# quad_decay_v1_0_1.net
KiCad netlist of a schematic drawn in EAGLE
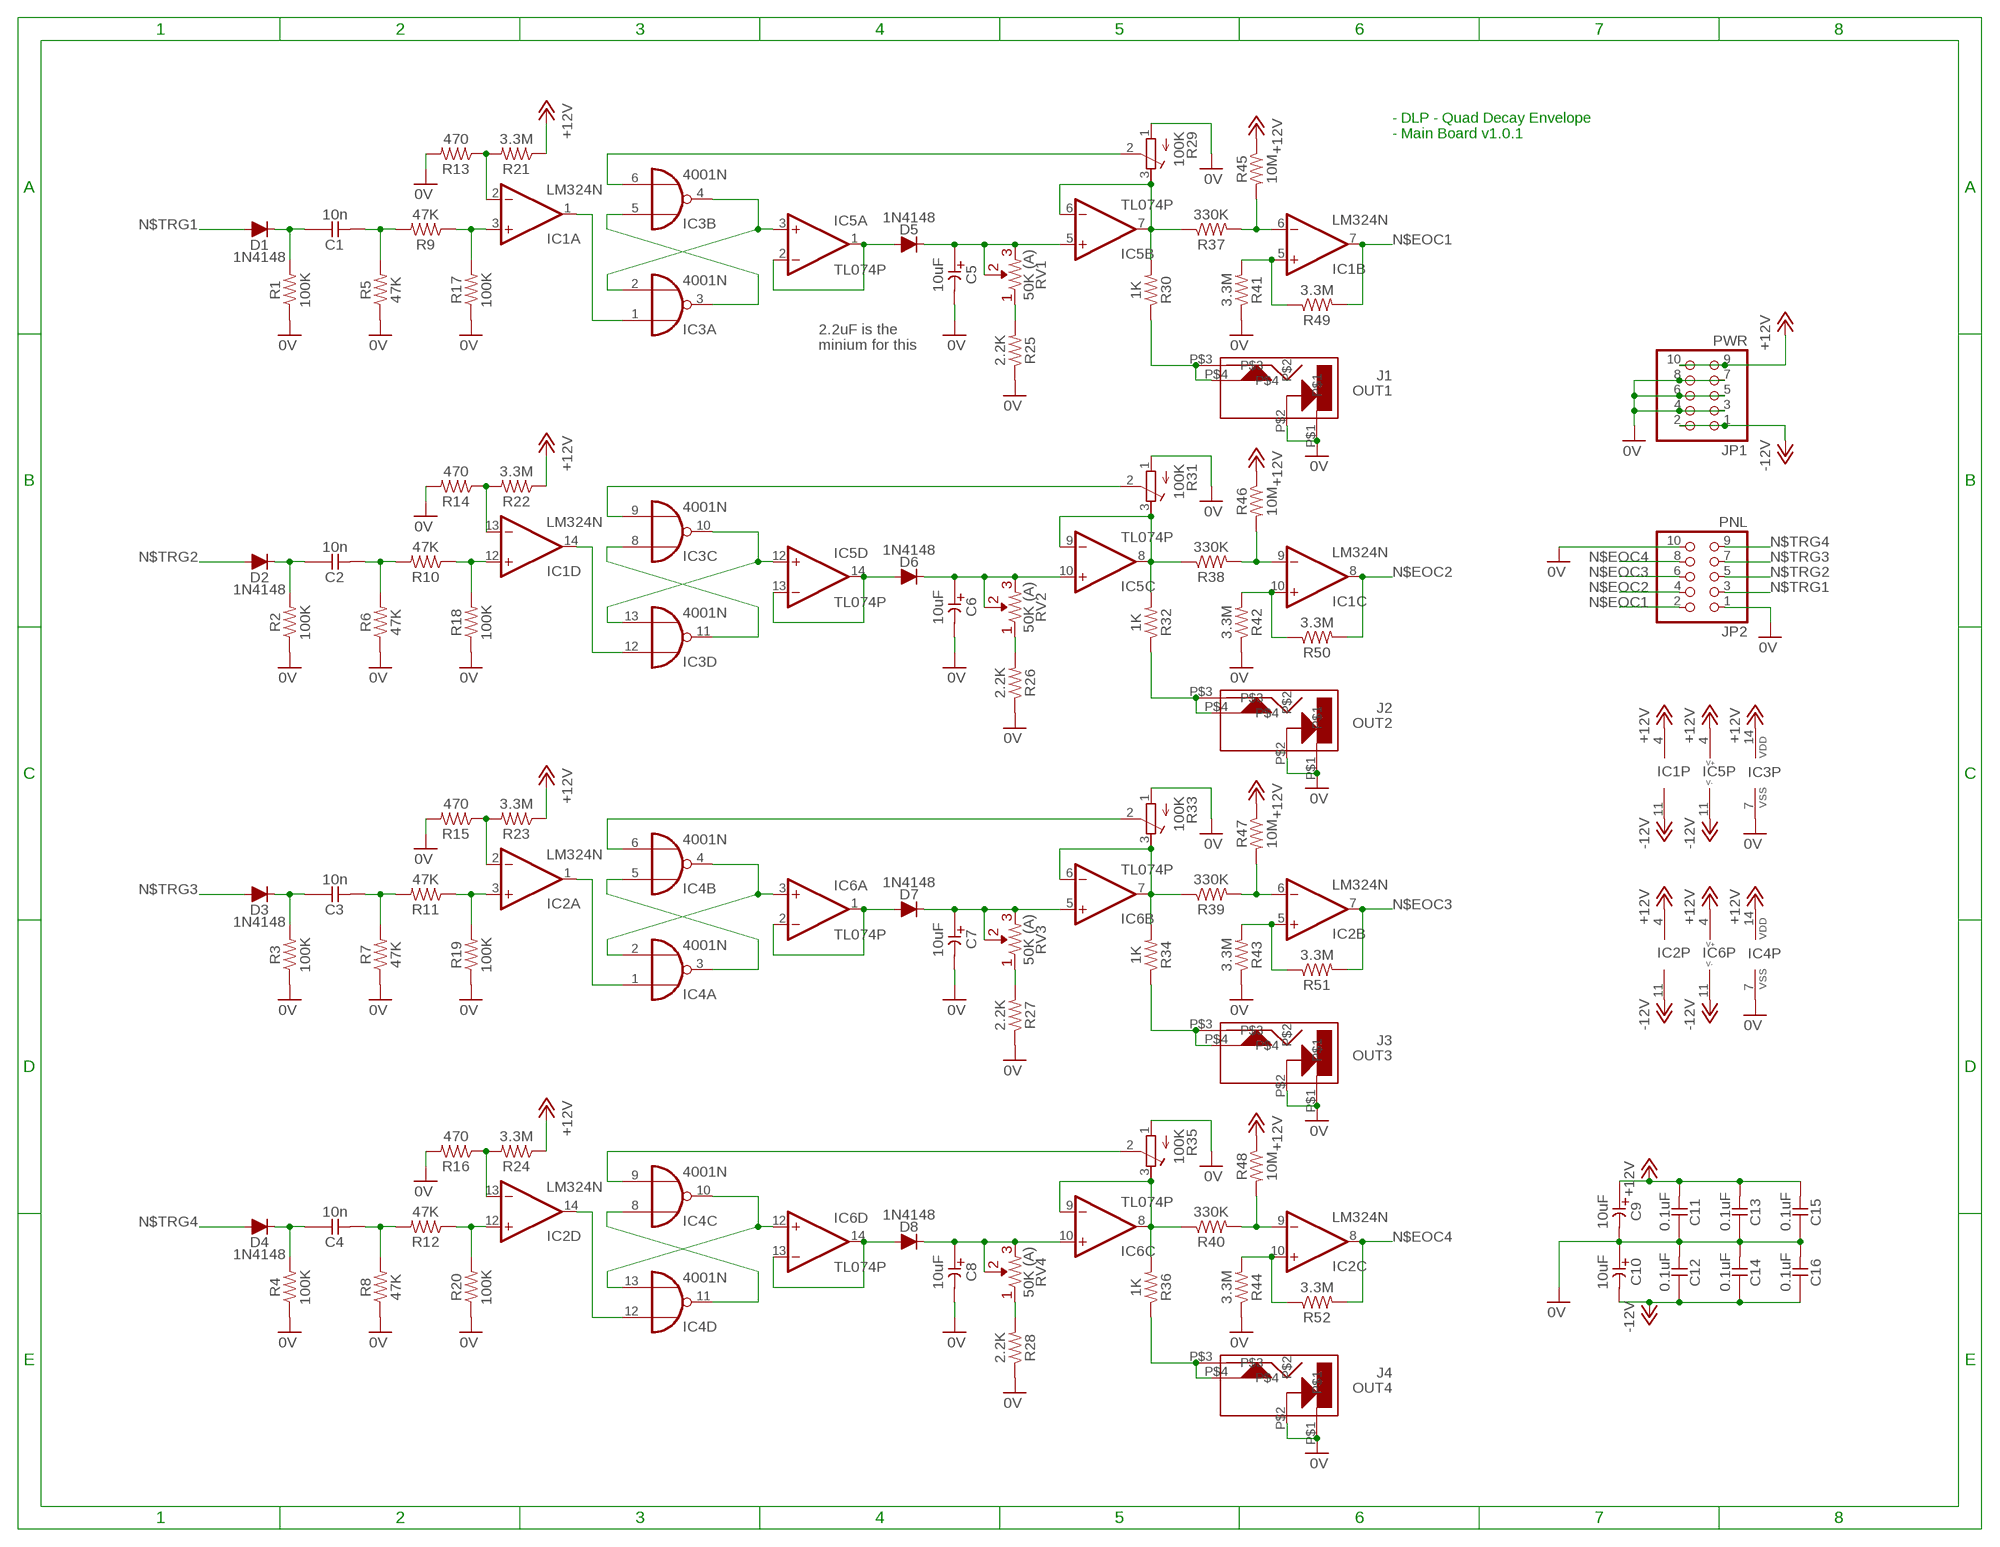
[diagram p0: schematic, sheet 1]

(export (version "E")
  (design (tool "Eeschema 10.0.6"))
  (components
    (comp (ref "C1")
      (value "10n")
      (footprint "eagle-import:C025-024X044")
      (libsource (lib "eagle-import") (part "CC-US025-024X044"))
    )
    (comp (ref "C2")
      (value "10n")
      (footprint "eagle-import:C025-024X044")
      (libsource (lib "eagle-import") (part "CC-US025-024X044"))
    )
    (comp (ref "C3")
      (value "10n")
      (footprint "eagle-import:C025-024X044")
      (libsource (lib "eagle-import") (part "CC-US025-024X044"))
    )
    (comp (ref "C4")
      (value "10n")
      (footprint "eagle-import:C025-024X044")
      (libsource (lib "eagle-import") (part "CC-US025-024X044"))
    )
    (comp (ref "C5")
      (value "10uF")
      (footprint "eagle-import:E2-5")
      (libsource (lib "eagle-import") (part "CE-USE2-5"))
    )
    (comp (ref "C6")
      (value "10uF")
      (footprint "eagle-import:E2-5")
      (libsource (lib "eagle-import") (part "CE-USE2-5"))
    )
    (comp (ref "C7")
      (value "10uF")
      (footprint "eagle-import:E2-5")
      (libsource (lib "eagle-import") (part "CE-USE2-5"))
    )
    (comp (ref "C8")
      (value "10uF")
      (footprint "eagle-import:E2-5")
      (libsource (lib "eagle-import") (part "CE-USE2-5"))
    )
    (comp (ref "C9")
      (value "10uF")
      (footprint "eagle-import:E2-5")
      (libsource (lib "eagle-import") (part "CE-USE2-5"))
    )
    (comp (ref "C10")
      (value "10uF")
      (footprint "eagle-import:E2-5")
      (libsource (lib "eagle-import") (part "CE-USE2-5"))
    )
    (comp (ref "C11")
      (value "0.1uF")
      (footprint "eagle-import:C025-024X044")
      (libsource (lib "eagle-import") (part "CC-US025-024X044"))
    )
    (comp (ref "C12")
      (value "0.1uF")
      (footprint "eagle-import:C025-024X044")
      (libsource (lib "eagle-import") (part "CC-US025-024X044"))
    )
    (comp (ref "C13")
      (value "0.1uF")
      (footprint "eagle-import:C025-024X044")
      (libsource (lib "eagle-import") (part "CC-US025-024X044"))
    )
    (comp (ref "C14")
      (value "0.1uF")
      (footprint "eagle-import:C025-024X044")
      (libsource (lib "eagle-import") (part "CC-US025-024X044"))
    )
    (comp (ref "C15")
      (value "0.1uF")
      (footprint "eagle-import:C025-024X044")
      (libsource (lib "eagle-import") (part "CC-US025-024X044"))
    )
    (comp (ref "C16")
      (value "0.1uF")
      (footprint "eagle-import:C025-024X044")
      (libsource (lib "eagle-import") (part "CC-US025-024X044"))
    )
    (comp (ref "D1")
      (value "1N4148")
      (footprint "eagle-import:DO34-5")
      (libsource (lib "eagle-import") (part "1N4148"))
    )
    (comp (ref "D2")
      (value "1N4148")
      (footprint "eagle-import:DO34-5")
      (libsource (lib "eagle-import") (part "1N4148"))
    )
    (comp (ref "D3")
      (value "1N4148")
      (footprint "eagle-import:DO34-5")
      (libsource (lib "eagle-import") (part "1N4148"))
    )
    (comp (ref "D4")
      (value "1N4148")
      (footprint "eagle-import:DO34-5")
      (libsource (lib "eagle-import") (part "1N4148"))
    )
    (comp (ref "D5")
      (value "1N4148")
      (footprint "eagle-import:DO34-5")
      (libsource (lib "eagle-import") (part "1N4148"))
    )
    (comp (ref "D6")
      (value "1N4148")
      (footprint "eagle-import:DO34-5")
      (libsource (lib "eagle-import") (part "1N4148"))
    )
    (comp (ref "D7")
      (value "1N4148")
      (footprint "eagle-import:DO34-5")
      (libsource (lib "eagle-import") (part "1N4148"))
    )
    (comp (ref "D8")
      (value "1N4148")
      (footprint "eagle-import:DO34-5")
      (libsource (lib "eagle-import") (part "1N4148"))
    )
    (comp (ref "IC1")
      (value "LM324N")
      (footprint "eagle-import:DIL14")
      (libsource (lib "eagle-import") (part "LM324N"))
    )
    (comp (ref "IC2")
      (value "LM324N")
      (footprint "eagle-import:DIL14")
      (libsource (lib "eagle-import") (part "LM324N"))
    )
    (comp (ref "IC3")
      (value "4001N")
      (footprint "eagle-import:DIL14")
      (libsource (lib "eagle-import") (part "4001N"))
    )
    (comp (ref "IC4")
      (value "4001N")
      (footprint "eagle-import:DIL14")
      (libsource (lib "eagle-import") (part "4001N"))
    )
    (comp (ref "IC5")
      (value "TL074P")
      (footprint "eagle-import:DIL14")
      (libsource (lib "eagle-import") (part "TL074P"))
    )
    (comp (ref "IC6")
      (value "TL074P")
      (footprint "eagle-import:DIL14")
      (libsource (lib "eagle-import") (part "TL074P"))
    )
    (comp (ref "J1")
      (value "OUT1")
      (footprint "eagle-import:CL1384")
      (libsource (lib "eagle-import") (part "CL1384"))
    )
    (comp (ref "J2")
      (value "OUT2")
      (footprint "eagle-import:CL1384")
      (libsource (lib "eagle-import") (part "CL1384"))
    )
    (comp (ref "J3")
      (value "OUT3")
      (footprint "eagle-import:CL1384")
      (libsource (lib "eagle-import") (part "CL1384"))
    )
    (comp (ref "J4")
      (value "OUT4")
      (footprint "eagle-import:CL1384")
      (libsource (lib "eagle-import") (part "CL1384"))
    )
    (comp (ref "JP1")
      (value "PWR")
      (footprint "eagle-import:2X05")
      (libsource (lib "eagle-import") (part "PINHD-2X5"))
    )
    (comp (ref "JP2")
      (value "PNL")
      (footprint "eagle-import:2X05")
      (libsource (lib "eagle-import") (part "PINHD-2X5"))
    )
    (comp (ref "R1")
      (value "100K")
      (footprint "eagle-import:0207_7")
      (libsource (lib "eagle-import") (part "R"))
    )
    (comp (ref "R2")
      (value "100K")
      (footprint "eagle-import:0207_7")
      (libsource (lib "eagle-import") (part "R"))
    )
    (comp (ref "R3")
      (value "100K")
      (footprint "eagle-import:0207_7")
      (libsource (lib "eagle-import") (part "R"))
    )
    (comp (ref "R4")
      (value "100K")
      (footprint "eagle-import:0207_7")
      (libsource (lib "eagle-import") (part "R"))
    )
    (comp (ref "R5")
      (value "47K")
      (footprint "eagle-import:0207_7")
      (libsource (lib "eagle-import") (part "R"))
    )
    (comp (ref "R6")
      (value "47K")
      (footprint "eagle-import:0207_7")
      (libsource (lib "eagle-import") (part "R"))
    )
    (comp (ref "R7")
      (value "47K")
      (footprint "eagle-import:0207_7")
      (libsource (lib "eagle-import") (part "R"))
    )
    (comp (ref "R8")
      (value "47K")
      (footprint "eagle-import:0207_7")
      (libsource (lib "eagle-import") (part "R"))
    )
    (comp (ref "R9")
      (value "47K")
      (footprint "eagle-import:0207_7")
      (libsource (lib "eagle-import") (part "R"))
    )
    (comp (ref "R10")
      (value "47K")
      (footprint "eagle-import:0207_7")
      (libsource (lib "eagle-import") (part "R"))
    )
    (comp (ref "R11")
      (value "47K")
      (footprint "eagle-import:0207_7")
      (libsource (lib "eagle-import") (part "R"))
    )
    (comp (ref "R12")
      (value "47K")
      (footprint "eagle-import:0207_7")
      (libsource (lib "eagle-import") (part "R"))
    )
    (comp (ref "R13")
      (value "470")
      (footprint "eagle-import:0207_7")
      (libsource (lib "eagle-import") (part "R"))
    )
    (comp (ref "R14")
      (value "470")
      (footprint "eagle-import:0207_7")
      (libsource (lib "eagle-import") (part "R"))
    )
    (comp (ref "R15")
      (value "470")
      (footprint "eagle-import:0207_7")
      (libsource (lib "eagle-import") (part "R"))
    )
    (comp (ref "R16")
      (value "470")
      (footprint "eagle-import:0207_7")
      (libsource (lib "eagle-import") (part "R"))
    )
    (comp (ref "R17")
      (value "100K")
      (footprint "eagle-import:0207_7")
      (libsource (lib "eagle-import") (part "R"))
    )
    (comp (ref "R18")
      (value "100K")
      (footprint "eagle-import:0207_7")
      (libsource (lib "eagle-import") (part "R"))
    )
    (comp (ref "R19")
      (value "100K")
      (footprint "eagle-import:0207_7")
      (libsource (lib "eagle-import") (part "R"))
    )
    (comp (ref "R20")
      (value "100K")
      (footprint "eagle-import:0207_7")
      (libsource (lib "eagle-import") (part "R"))
    )
    (comp (ref "R21")
      (value "3.3M")
      (footprint "eagle-import:0207_7")
      (libsource (lib "eagle-import") (part "R"))
    )
    (comp (ref "R22")
      (value "3.3M")
      (footprint "eagle-import:0207_7")
      (libsource (lib "eagle-import") (part "R"))
    )
    (comp (ref "R23")
      (value "3.3M")
      (footprint "eagle-import:0207_7")
      (libsource (lib "eagle-import") (part "R"))
    )
    (comp (ref "R24")
      (value "3.3M")
      (footprint "eagle-import:0207_7")
      (libsource (lib "eagle-import") (part "R"))
    )
    (comp (ref "R25")
      (value "2.2K")
      (footprint "eagle-import:0207_7")
      (libsource (lib "eagle-import") (part "R"))
    )
    (comp (ref "R26")
      (value "2.2K")
      (footprint "eagle-import:0207_7")
      (libsource (lib "eagle-import") (part "R"))
    )
    (comp (ref "R27")
      (value "2.2K")
      (footprint "eagle-import:0207_7")
      (libsource (lib "eagle-import") (part "R"))
    )
    (comp (ref "R28")
      (value "2.2K")
      (footprint "eagle-import:0207_7")
      (libsource (lib "eagle-import") (part "R"))
    )
    (comp (ref "R29")
      (value "100K")
      (footprint "eagle-import:RTRIM3339P")
      (libsource (lib "eagle-import") (part "R-TRIMM3339P"))
    )
    (comp (ref "R30")
      (value "1K")
      (footprint "eagle-import:0207_7")
      (libsource (lib "eagle-import") (part "R"))
    )
    (comp (ref "R31")
      (value "100K")
      (footprint "eagle-import:RTRIM3339P")
      (libsource (lib "eagle-import") (part "R-TRIMM3339P"))
    )
    (comp (ref "R32")
      (value "1K")
      (footprint "eagle-import:0207_7")
      (libsource (lib "eagle-import") (part "R"))
    )
    (comp (ref "R33")
      (value "100K")
      (footprint "eagle-import:RTRIM3339P")
      (libsource (lib "eagle-import") (part "R-TRIMM3339P"))
    )
    (comp (ref "R34")
      (value "1K")
      (footprint "eagle-import:0207_7")
      (libsource (lib "eagle-import") (part "R"))
    )
    (comp (ref "R35")
      (value "100K")
      (footprint "eagle-import:RTRIM3339P")
      (libsource (lib "eagle-import") (part "R-TRIMM3339P"))
    )
    (comp (ref "R36")
      (value "1K")
      (footprint "eagle-import:0207_7")
      (libsource (lib "eagle-import") (part "R"))
    )
    (comp (ref "R37")
      (value "330K")
      (footprint "eagle-import:0207_7")
      (libsource (lib "eagle-import") (part "R"))
    )
    (comp (ref "R38")
      (value "330K")
      (footprint "eagle-import:0207_7")
      (libsource (lib "eagle-import") (part "R"))
    )
    (comp (ref "R39")
      (value "330K")
      (footprint "eagle-import:0207_7")
      (libsource (lib "eagle-import") (part "R"))
    )
    (comp (ref "R40")
      (value "330K")
      (footprint "eagle-import:0207_7")
      (libsource (lib "eagle-import") (part "R"))
    )
    (comp (ref "R41")
      (value "3.3M")
      (footprint "eagle-import:0207_7")
      (libsource (lib "eagle-import") (part "R"))
    )
    (comp (ref "R42")
      (value "3.3M")
      (footprint "eagle-import:0207_7")
      (libsource (lib "eagle-import") (part "R"))
    )
    (comp (ref "R43")
      (value "3.3M")
      (footprint "eagle-import:0207_7")
      (libsource (lib "eagle-import") (part "R"))
    )
    (comp (ref "R44")
      (value "3.3M")
      (footprint "eagle-import:0207_7")
      (libsource (lib "eagle-import") (part "R"))
    )
    (comp (ref "R45")
      (value "10M")
      (footprint "eagle-import:0207_7")
      (libsource (lib "eagle-import") (part "R"))
    )
    (comp (ref "R46")
      (value "10M")
      (footprint "eagle-import:0207_7")
      (libsource (lib "eagle-import") (part "R"))
    )
    (comp (ref "R47")
      (value "10M")
      (footprint "eagle-import:0207_7")
      (libsource (lib "eagle-import") (part "R"))
    )
    (comp (ref "R48")
      (value "10M")
      (footprint "eagle-import:0207_7")
      (libsource (lib "eagle-import") (part "R"))
    )
    (comp (ref "R49")
      (value "3.3M")
      (footprint "eagle-import:0207_7")
      (libsource (lib "eagle-import") (part "R"))
    )
    (comp (ref "R50")
      (value "3.3M")
      (footprint "eagle-import:0207_7")
      (libsource (lib "eagle-import") (part "R"))
    )
    (comp (ref "R51")
      (value "3.3M")
      (footprint "eagle-import:0207_7")
      (libsource (lib "eagle-import") (part "R"))
    )
    (comp (ref "R52")
      (value "3.3M")
      (footprint "eagle-import:0207_7")
      (libsource (lib "eagle-import") (part "R"))
    )
    (comp (ref "RV1")
      (value "50K (A)")
      (footprint "eagle-import:R-VAR")
      (libsource (lib "eagle-import") (part "R-VAR"))
    )
    (comp (ref "RV2")
      (value "50K (A)")
      (footprint "eagle-import:R-VAR")
      (libsource (lib "eagle-import") (part "R-VAR"))
    )
    (comp (ref "RV3")
      (value "50K (A)")
      (footprint "eagle-import:R-VAR")
      (libsource (lib "eagle-import") (part "R-VAR"))
    )
    (comp (ref "RV4")
      (value "50K (A)")
      (footprint "eagle-import:R-VAR")
      (libsource (lib "eagle-import") (part "R-VAR"))
    )
  )
  (nets
    (net (code "1") (name "+12V") (class "Default")
      (node (ref "C11") (pin "2") (pinfunction "2_2") (pintype "passive"))
      (node (ref "C13") (pin "2") (pinfunction "2_2") (pintype "passive"))
      (node (ref "C15") (pin "2") (pinfunction "2_2") (pintype "passive"))
      (node (ref "C9") (pin "+") (pinfunction "+_+") (pintype "passive"))
      (node (ref "IC1") (pin "4") (pinfunction "V+_4") (pintype "power_in"))
      (node (ref "IC2") (pin "4") (pinfunction "V+_4") (pintype "power_in"))
      (node (ref "IC3") (pin "14") (pinfunction "VDD_14") (pintype "power_in"))
      (node (ref "IC4") (pin "14") (pinfunction "VDD_14") (pintype "power_in"))
      (node (ref "IC5") (pin "4") (pinfunction "V+_4") (pintype "power_in"))
      (node (ref "IC6") (pin "4") (pinfunction "V+_4") (pintype "power_in"))
      (node (ref "JP1") (pin "10") (pinfunction "10_10") (pintype "passive"))
      (node (ref "JP1") (pin "9") (pinfunction "9_9") (pintype "passive"))
      (node (ref "R21") (pin "1") (pinfunction "1_1") (pintype "passive"))
      (node (ref "R22") (pin "1") (pinfunction "1_1") (pintype "passive"))
      (node (ref "R23") (pin "1") (pinfunction "1_1") (pintype "passive"))
      (node (ref "R24") (pin "1") (pinfunction "1_1") (pintype "passive"))
      (node (ref "R45") (pin "1") (pinfunction "1_1") (pintype "passive"))
      (node (ref "R46") (pin "1") (pinfunction "1_1") (pintype "passive"))
      (node (ref "R47") (pin "1") (pinfunction "1_1") (pintype "passive"))
      (node (ref "R48") (pin "1") (pinfunction "1_1") (pintype "passive"))
    )
    (net (code "2") (name "-12V") (class "Default")
      (node (ref "C10") (pin "-") (pinfunction "-_-") (pintype "passive"))
      (node (ref "C12") (pin "1") (pinfunction "1_1") (pintype "passive"))
      (node (ref "C14") (pin "1") (pinfunction "1_1") (pintype "passive"))
      (node (ref "C16") (pin "1") (pinfunction "1_1") (pintype "passive"))
      (node (ref "IC1") (pin "11") (pinfunction "V-_11") (pintype "power_in"))
      (node (ref "IC2") (pin "11") (pinfunction "V-_11") (pintype "power_in"))
      (node (ref "IC5") (pin "11") (pinfunction "V-_11") (pintype "power_in"))
      (node (ref "IC6") (pin "11") (pinfunction "V-_11") (pintype "power_in"))
      (node (ref "JP1") (pin "1") (pinfunction "1_1") (pintype "passive"))
      (node (ref "JP1") (pin "2") (pinfunction "2_2") (pintype "passive"))
    )
    (net (code "3") (name "/N$EOC1") (class "Default")
      (node (ref "IC1") (pin "7") (pinfunction "OUT_7") (pintype "output"))
      (node (ref "JP2") (pin "2") (pinfunction "2_2") (pintype "passive"))
      (node (ref "R49") (pin "2") (pinfunction "2_2") (pintype "passive"))
    )
    (net (code "4") (name "/N$EOC2") (class "Default")
      (node (ref "IC1") (pin "8") (pinfunction "OUT_8") (pintype "output"))
      (node (ref "JP2") (pin "4") (pinfunction "4_4") (pintype "passive"))
      (node (ref "R50") (pin "2") (pinfunction "2_2") (pintype "passive"))
    )
    (net (code "5") (name "/N$EOC3") (class "Default")
      (node (ref "IC2") (pin "7") (pinfunction "OUT_7") (pintype "output"))
      (node (ref "JP2") (pin "6") (pinfunction "6_6") (pintype "passive"))
      (node (ref "R51") (pin "2") (pinfunction "2_2") (pintype "passive"))
    )
    (net (code "6") (name "/N$EOC4") (class "Default")
      (node (ref "IC2") (pin "8") (pinfunction "OUT_8") (pintype "output"))
      (node (ref "JP2") (pin "8") (pinfunction "8_8") (pintype "passive"))
      (node (ref "R52") (pin "2") (pinfunction "2_2") (pintype "passive"))
    )
    (net (code "7") (name "/N$TRG1") (class "Default")
      (node (ref "D1") (pin "A") (pinfunction "A_A") (pintype "passive"))
      (node (ref "JP2") (pin "3") (pinfunction "3_3") (pintype "passive"))
    )
    (net (code "8") (name "/N$TRG2") (class "Default")
      (node (ref "D2") (pin "A") (pinfunction "A_A") (pintype "passive"))
      (node (ref "JP2") (pin "5") (pinfunction "5_5") (pintype "passive"))
    )
    (net (code "9") (name "/N$TRG3") (class "Default")
      (node (ref "D3") (pin "A") (pinfunction "A_A") (pintype "passive"))
      (node (ref "JP2") (pin "7") (pinfunction "7_7") (pintype "passive"))
    )
    (net (code "10") (name "/N$TRG4") (class "Default")
      (node (ref "D4") (pin "A") (pinfunction "A_A") (pintype "passive"))
      (node (ref "JP2") (pin "9") (pinfunction "9_9") (pintype "passive"))
    )
    (net (code "11") (name "0V") (class "Default")
      (node (ref "C10") (pin "+") (pinfunction "+_+") (pintype "passive"))
      (node (ref "C11") (pin "1") (pinfunction "1_1") (pintype "passive"))
      (node (ref "C12") (pin "2") (pinfunction "2_2") (pintype "passive"))
      (node (ref "C13") (pin "1") (pinfunction "1_1") (pintype "passive"))
      (node (ref "C14") (pin "2") (pinfunction "2_2") (pintype "passive"))
      (node (ref "C15") (pin "1") (pinfunction "1_1") (pintype "passive"))
      (node (ref "C16") (pin "2") (pinfunction "2_2") (pintype "passive"))
      (node (ref "C5") (pin "-") (pinfunction "-_-") (pintype "passive"))
      (node (ref "C6") (pin "-") (pinfunction "-_-") (pintype "passive"))
      (node (ref "C7") (pin "-") (pinfunction "-_-") (pintype "passive"))
      (node (ref "C8") (pin "-") (pinfunction "-_-") (pintype "passive"))
      (node (ref "C9") (pin "-") (pinfunction "-_-") (pintype "passive"))
      (node (ref "IC3") (pin "7") (pinfunction "VSS_7") (pintype "power_in"))
      (node (ref "IC4") (pin "7") (pinfunction "VSS_7") (pintype "power_in"))
      (node (ref "J1") (pin "P$1") (pinfunction "P$1_P$1") (pintype "bidirectional"))
      (node (ref "J1") (pin "P$2") (pinfunction "P$2_P$2") (pintype "bidirectional"))
      (node (ref "J2") (pin "P$1") (pinfunction "P$1_P$1") (pintype "bidirectional"))
      (node (ref "J2") (pin "P$2") (pinfunction "P$2_P$2") (pintype "bidirectional"))
      (node (ref "J3") (pin "P$1") (pinfunction "P$1_P$1") (pintype "bidirectional"))
      (node (ref "J3") (pin "P$2") (pinfunction "P$2_P$2") (pintype "bidirectional"))
      (node (ref "J4") (pin "P$1") (pinfunction "P$1_P$1") (pintype "bidirectional"))
      (node (ref "J4") (pin "P$2") (pinfunction "P$2_P$2") (pintype "bidirectional"))
      (node (ref "JP1") (pin "3") (pinfunction "3_3") (pintype "passive"))
      (node (ref "JP1") (pin "4") (pinfunction "4_4") (pintype "passive"))
      (node (ref "JP1") (pin "5") (pinfunction "5_5") (pintype "passive"))
      (node (ref "JP1") (pin "6") (pinfunction "6_6") (pintype "passive"))
      (node (ref "JP1") (pin "7") (pinfunction "7_7") (pintype "passive"))
      (node (ref "JP1") (pin "8") (pinfunction "8_8") (pintype "passive"))
      (node (ref "JP2") (pin "1") (pinfunction "1_1") (pintype "passive"))
      (node (ref "JP2") (pin "10") (pinfunction "10_10") (pintype "passive"))
      (node (ref "R1") (pin "1") (pinfunction "1_1") (pintype "passive"))
      (node (ref "R13") (pin "2") (pinfunction "2_2") (pintype "passive"))
      (node (ref "R14") (pin "2") (pinfunction "2_2") (pintype "passive"))
      (node (ref "R15") (pin "2") (pinfunction "2_2") (pintype "passive"))
      (node (ref "R16") (pin "2") (pinfunction "2_2") (pintype "passive"))
      (node (ref "R17") (pin "1") (pinfunction "1_1") (pintype "passive"))
      (node (ref "R18") (pin "1") (pinfunction "1_1") (pintype "passive"))
      (node (ref "R19") (pin "1") (pinfunction "1_1") (pintype "passive"))
      (node (ref "R2") (pin "1") (pinfunction "1_1") (pintype "passive"))
      (node (ref "R20") (pin "1") (pinfunction "1_1") (pintype "passive"))
      (node (ref "R25") (pin "1") (pinfunction "1_1") (pintype "passive"))
      (node (ref "R26") (pin "1") (pinfunction "1_1") (pintype "passive"))
      (node (ref "R27") (pin "1") (pinfunction "1_1") (pintype "passive"))
      (node (ref "R28") (pin "1") (pinfunction "1_1") (pintype "passive"))
      (node (ref "R29") (pin "1") (pinfunction "A_1") (pintype "passive"))
      (node (ref "R3") (pin "1") (pinfunction "1_1") (pintype "passive"))
      (node (ref "R31") (pin "1") (pinfunction "A_1") (pintype "passive"))
      (node (ref "R33") (pin "1") (pinfunction "A_1") (pintype "passive"))
      (node (ref "R35") (pin "1") (pinfunction "A_1") (pintype "passive"))
      (node (ref "R4") (pin "1") (pinfunction "1_1") (pintype "passive"))
      (node (ref "R41") (pin "1") (pinfunction "1_1") (pintype "passive"))
      (node (ref "R42") (pin "1") (pinfunction "1_1") (pintype "passive"))
      (node (ref "R43") (pin "1") (pinfunction "1_1") (pintype "passive"))
      (node (ref "R44") (pin "1") (pinfunction "1_1") (pintype "passive"))
      (node (ref "R5") (pin "1") (pinfunction "1_1") (pintype "passive"))
      (node (ref "R6") (pin "1") (pinfunction "1_1") (pintype "passive"))
      (node (ref "R7") (pin "1") (pinfunction "1_1") (pintype "passive"))
      (node (ref "R8") (pin "1") (pinfunction "1_1") (pintype "passive"))
    )
    (net (code "12") (name "Net-(C1-Pad1)") (class "Default")
      (node (ref "C1") (pin "1") (pinfunction "1_1") (pintype "passive"))
      (node (ref "D1") (pin "C") (pinfunction "C_C") (pintype "passive"))
      (node (ref "R1") (pin "2") (pinfunction "2_2") (pintype "passive"))
    )
    (net (code "13") (name "Net-(C1-Pad2)") (class "Default")
      (node (ref "C1") (pin "2") (pinfunction "2_2") (pintype "passive"))
      (node (ref "R5") (pin "2") (pinfunction "2_2") (pintype "passive"))
      (node (ref "R9") (pin "2") (pinfunction "2_2") (pintype "passive"))
    )
    (net (code "14") (name "Net-(C2-Pad1)") (class "Default")
      (node (ref "C2") (pin "1") (pinfunction "1_1") (pintype "passive"))
      (node (ref "D2") (pin "C") (pinfunction "C_C") (pintype "passive"))
      (node (ref "R2") (pin "2") (pinfunction "2_2") (pintype "passive"))
    )
    (net (code "15") (name "Net-(C2-Pad2)") (class "Default")
      (node (ref "C2") (pin "2") (pinfunction "2_2") (pintype "passive"))
      (node (ref "R10") (pin "2") (pinfunction "2_2") (pintype "passive"))
      (node (ref "R6") (pin "2") (pinfunction "2_2") (pintype "passive"))
    )
    (net (code "16") (name "Net-(C3-Pad1)") (class "Default")
      (node (ref "C3") (pin "1") (pinfunction "1_1") (pintype "passive"))
      (node (ref "D3") (pin "C") (pinfunction "C_C") (pintype "passive"))
      (node (ref "R3") (pin "2") (pinfunction "2_2") (pintype "passive"))
    )
    (net (code "17") (name "Net-(C3-Pad2)") (class "Default")
      (node (ref "C3") (pin "2") (pinfunction "2_2") (pintype "passive"))
      (node (ref "R11") (pin "2") (pinfunction "2_2") (pintype "passive"))
      (node (ref "R7") (pin "2") (pinfunction "2_2") (pintype "passive"))
    )
    (net (code "18") (name "Net-(C4-Pad1)") (class "Default")
      (node (ref "C4") (pin "1") (pinfunction "1_1") (pintype "passive"))
      (node (ref "D4") (pin "C") (pinfunction "C_C") (pintype "passive"))
      (node (ref "R4") (pin "2") (pinfunction "2_2") (pintype "passive"))
    )
    (net (code "19") (name "Net-(C4-Pad2)") (class "Default")
      (node (ref "C4") (pin "2") (pinfunction "2_2") (pintype "passive"))
      (node (ref "R12") (pin "2") (pinfunction "2_2") (pintype "passive"))
      (node (ref "R8") (pin "2") (pinfunction "2_2") (pintype "passive"))
    )
    (net (code "20") (name "Net-(IC1A-+IN)") (class "Default")
      (node (ref "IC1") (pin "3") (pinfunction "+IN_3") (pintype "input"))
      (node (ref "R17") (pin "2") (pinfunction "2_2") (pintype "passive"))
      (node (ref "R9") (pin "1") (pinfunction "1_1") (pintype "passive"))
    )
    (net (code "21") (name "Net-(IC1A--IN)") (class "Default")
      (node (ref "IC1") (pin "2") (pinfunction "-IN_2") (pintype "input"))
      (node (ref "R13") (pin "1") (pinfunction "1_1") (pintype "passive"))
      (node (ref "R21") (pin "2") (pinfunction "2_2") (pintype "passive"))
    )
    (net (code "22") (name "Net-(IC1A-OUT)") (class "Default")
      (node (ref "IC1") (pin "1") (pinfunction "OUT_1") (pintype "output"))
      (node (ref "IC3") (pin "1") (pinfunction "I0_1") (pintype "input"))
    )
    (net (code "23") (name "Net-(IC1B-+IN)") (class "Default")
      (node (ref "IC1") (pin "5") (pinfunction "+IN_5") (pintype "input"))
      (node (ref "R41") (pin "2") (pinfunction "2_2") (pintype "passive"))
      (node (ref "R49") (pin "1") (pinfunction "1_1") (pintype "passive"))
    )
    (net (code "24") (name "Net-(IC1B--IN)") (class "Default")
      (node (ref "IC1") (pin "6") (pinfunction "-IN_6") (pintype "input"))
      (node (ref "R37") (pin "2") (pinfunction "2_2") (pintype "passive"))
      (node (ref "R45") (pin "2") (pinfunction "2_2") (pintype "passive"))
    )
    (net (code "25") (name "Net-(IC1C-+IN)") (class "Default")
      (node (ref "IC1") (pin "10") (pinfunction "+IN_10") (pintype "input"))
      (node (ref "R42") (pin "2") (pinfunction "2_2") (pintype "passive"))
      (node (ref "R50") (pin "1") (pinfunction "1_1") (pintype "passive"))
    )
    (net (code "26") (name "Net-(IC1C--IN)") (class "Default")
      (node (ref "IC1") (pin "9") (pinfunction "-IN_9") (pintype "input"))
      (node (ref "R38") (pin "2") (pinfunction "2_2") (pintype "passive"))
      (node (ref "R46") (pin "2") (pinfunction "2_2") (pintype "passive"))
    )
    (net (code "27") (name "Net-(IC1D-+IN)") (class "Default")
      (node (ref "IC1") (pin "12") (pinfunction "+IN_12") (pintype "input"))
      (node (ref "R10") (pin "1") (pinfunction "1_1") (pintype "passive"))
      (node (ref "R18") (pin "2") (pinfunction "2_2") (pintype "passive"))
    )
    (net (code "28") (name "Net-(IC1D--IN)") (class "Default")
      (node (ref "IC1") (pin "13") (pinfunction "-IN_13") (pintype "input"))
      (node (ref "R14") (pin "1") (pinfunction "1_1") (pintype "passive"))
      (node (ref "R22") (pin "2") (pinfunction "2_2") (pintype "passive"))
    )
    (net (code "29") (name "Net-(IC1D-OUT)") (class "Default")
      (node (ref "IC1") (pin "14") (pinfunction "OUT_14") (pintype "output"))
      (node (ref "IC3") (pin "12") (pinfunction "I0_12") (pintype "input"))
    )
    (net (code "30") (name "Net-(IC2A-+IN)") (class "Default")
      (node (ref "IC2") (pin "3") (pinfunction "+IN_3") (pintype "input"))
      (node (ref "R11") (pin "1") (pinfunction "1_1") (pintype "passive"))
      (node (ref "R19") (pin "2") (pinfunction "2_2") (pintype "passive"))
    )
    (net (code "31") (name "Net-(IC2A--IN)") (class "Default")
      (node (ref "IC2") (pin "2") (pinfunction "-IN_2") (pintype "input"))
      (node (ref "R15") (pin "1") (pinfunction "1_1") (pintype "passive"))
      (node (ref "R23") (pin "2") (pinfunction "2_2") (pintype "passive"))
    )
    (net (code "32") (name "Net-(IC2A-OUT)") (class "Default")
      (node (ref "IC2") (pin "1") (pinfunction "OUT_1") (pintype "output"))
      (node (ref "IC4") (pin "1") (pinfunction "I0_1") (pintype "input"))
    )
    (net (code "33") (name "Net-(IC2B-+IN)") (class "Default")
      (node (ref "IC2") (pin "5") (pinfunction "+IN_5") (pintype "input"))
      (node (ref "R43") (pin "2") (pinfunction "2_2") (pintype "passive"))
      (node (ref "R51") (pin "1") (pinfunction "1_1") (pintype "passive"))
    )
    (net (code "34") (name "Net-(IC2B--IN)") (class "Default")
      (node (ref "IC2") (pin "6") (pinfunction "-IN_6") (pintype "input"))
      (node (ref "R39") (pin "2") (pinfunction "2_2") (pintype "passive"))
      (node (ref "R47") (pin "2") (pinfunction "2_2") (pintype "passive"))
    )
    (net (code "35") (name "Net-(IC2C-+IN)") (class "Default")
      (node (ref "IC2") (pin "10") (pinfunction "+IN_10") (pintype "input"))
      (node (ref "R44") (pin "2") (pinfunction "2_2") (pintype "passive"))
      (node (ref "R52") (pin "1") (pinfunction "1_1") (pintype "passive"))
    )
    (net (code "36") (name "Net-(IC2C--IN)") (class "Default")
      (node (ref "IC2") (pin "9") (pinfunction "-IN_9") (pintype "input"))
      (node (ref "R40") (pin "2") (pinfunction "2_2") (pintype "passive"))
      (node (ref "R48") (pin "2") (pinfunction "2_2") (pintype "passive"))
    )
    (net (code "37") (name "Net-(IC2D-+IN)") (class "Default")
      (node (ref "IC2") (pin "12") (pinfunction "+IN_12") (pintype "input"))
      (node (ref "R12") (pin "1") (pinfunction "1_1") (pintype "passive"))
      (node (ref "R20") (pin "2") (pinfunction "2_2") (pintype "passive"))
    )
    (net (code "38") (name "Net-(IC2D--IN)") (class "Default")
      (node (ref "IC2") (pin "13") (pinfunction "-IN_13") (pintype "input"))
      (node (ref "R16") (pin "1") (pinfunction "1_1") (pintype "passive"))
      (node (ref "R24") (pin "2") (pinfunction "2_2") (pintype "passive"))
    )
    (net (code "39") (name "Net-(IC2D-OUT)") (class "Default")
      (node (ref "IC2") (pin "14") (pinfunction "OUT_14") (pintype "output"))
      (node (ref "IC4") (pin "12") (pinfunction "I0_12") (pintype "input"))
    )
    (net (code "40") (name "Net-(IC3A-I1)") (class "Default")
      (node (ref "IC3") (pin "2") (pinfunction "I1_2") (pintype "input"))
      (node (ref "IC3") (pin "4") (pinfunction "O_4") (pintype "output"))
      (node (ref "IC5") (pin "3") (pinfunction "+IN_3") (pintype "input"))
    )
    (net (code "41") (name "Net-(IC3A-O)") (class "Default")
      (node (ref "IC3") (pin "3") (pinfunction "O_3") (pintype "output"))
      (node (ref "IC3") (pin "5") (pinfunction "I0_5") (pintype "input"))
    )
    (net (code "42") (name "Net-(IC3B-I1)") (class "Default")
      (node (ref "IC3") (pin "6") (pinfunction "I1_6") (pintype "input"))
      (node (ref "R29") (pin "2") (pinfunction "S_2") (pintype "passive"))
    )
    (net (code "43") (name "Net-(IC3C-I0)") (class "Default")
      (node (ref "IC3") (pin "11") (pinfunction "O_11") (pintype "output"))
      (node (ref "IC3") (pin "8") (pinfunction "I0_8") (pintype "input"))
    )
    (net (code "44") (name "Net-(IC3C-I1)") (class "Default")
      (node (ref "IC3") (pin "9") (pinfunction "I1_9") (pintype "input"))
      (node (ref "R31") (pin "2") (pinfunction "S_2") (pintype "passive"))
    )
    (net (code "45") (name "Net-(IC3C-O)") (class "Default")
      (node (ref "IC3") (pin "10") (pinfunction "O_10") (pintype "output"))
      (node (ref "IC3") (pin "13") (pinfunction "I1_13") (pintype "input"))
      (node (ref "IC5") (pin "12") (pinfunction "+IN_12") (pintype "input"))
    )
    (net (code "46") (name "Net-(IC4A-I1)") (class "Default")
      (node (ref "IC4") (pin "2") (pinfunction "I1_2") (pintype "input"))
      (node (ref "IC4") (pin "4") (pinfunction "O_4") (pintype "output"))
      (node (ref "IC6") (pin "3") (pinfunction "+IN_3") (pintype "input"))
    )
    (net (code "47") (name "Net-(IC4A-O)") (class "Default")
      (node (ref "IC4") (pin "3") (pinfunction "O_3") (pintype "output"))
      (node (ref "IC4") (pin "5") (pinfunction "I0_5") (pintype "input"))
    )
    (net (code "48") (name "Net-(IC4B-I1)") (class "Default")
      (node (ref "IC4") (pin "6") (pinfunction "I1_6") (pintype "input"))
      (node (ref "R33") (pin "2") (pinfunction "S_2") (pintype "passive"))
    )
    (net (code "49") (name "Net-(IC4C-I0)") (class "Default")
      (node (ref "IC4") (pin "11") (pinfunction "O_11") (pintype "output"))
      (node (ref "IC4") (pin "8") (pinfunction "I0_8") (pintype "input"))
    )
    (net (code "50") (name "Net-(IC4C-I1)") (class "Default")
      (node (ref "IC4") (pin "9") (pinfunction "I1_9") (pintype "input"))
      (node (ref "R35") (pin "2") (pinfunction "S_2") (pintype "passive"))
    )
    (net (code "51") (name "Net-(IC4C-O)") (class "Default")
      (node (ref "IC4") (pin "10") (pinfunction "O_10") (pintype "output"))
      (node (ref "IC4") (pin "13") (pinfunction "I1_13") (pintype "input"))
      (node (ref "IC6") (pin "12") (pinfunction "+IN_12") (pintype "input"))
    )
    (net (code "52") (name "Net-(IC5A--IN)") (class "Default")
      (node (ref "D5") (pin "A") (pinfunction "A_A") (pintype "passive"))
      (node (ref "IC5") (pin "1") (pinfunction "OUT_1") (pintype "output"))
      (node (ref "IC5") (pin "2") (pinfunction "-IN_2") (pintype "input"))
    )
    (net (code "53") (name "Net-(IC5B-+IN)") (class "Default")
      (node (ref "C5") (pin "+") (pinfunction "+_+") (pintype "passive"))
      (node (ref "D5") (pin "C") (pinfunction "C_C") (pintype "passive"))
      (node (ref "IC5") (pin "5") (pinfunction "+IN_5") (pintype "input"))
      (node (ref "RV1") (pin "R2") (pinfunction "2_R2") (pintype "passive"))
      (node (ref "RV1") (pin "VAR") (pinfunction "P$1_VAR") (pintype "passive"))
    )
    (net (code "54") (name "Net-(IC5B--IN)") (class "Default")
      (node (ref "IC5") (pin "6") (pinfunction "-IN_6") (pintype "input"))
      (node (ref "IC5") (pin "7") (pinfunction "OUT_7") (pintype "output"))
      (node (ref "R29") (pin "3") (pinfunction "E_3") (pintype "passive"))
      (node (ref "R30") (pin "2") (pinfunction "2_2") (pintype "passive"))
      (node (ref "R37") (pin "1") (pinfunction "1_1") (pintype "passive"))
    )
    (net (code "55") (name "Net-(IC5C-+IN)") (class "Default")
      (node (ref "C6") (pin "+") (pinfunction "+_+") (pintype "passive"))
      (node (ref "D6") (pin "C") (pinfunction "C_C") (pintype "passive"))
      (node (ref "IC5") (pin "10") (pinfunction "+IN_10") (pintype "input"))
      (node (ref "RV2") (pin "R2") (pinfunction "2_R2") (pintype "passive"))
      (node (ref "RV2") (pin "VAR") (pinfunction "P$1_VAR") (pintype "passive"))
    )
    (net (code "56") (name "Net-(IC5C--IN)") (class "Default")
      (node (ref "IC5") (pin "8") (pinfunction "OUT_8") (pintype "output"))
      (node (ref "IC5") (pin "9") (pinfunction "-IN_9") (pintype "input"))
      (node (ref "R31") (pin "3") (pinfunction "E_3") (pintype "passive"))
      (node (ref "R32") (pin "2") (pinfunction "2_2") (pintype "passive"))
      (node (ref "R38") (pin "1") (pinfunction "1_1") (pintype "passive"))
    )
    (net (code "57") (name "Net-(IC5D--IN)") (class "Default")
      (node (ref "D6") (pin "A") (pinfunction "A_A") (pintype "passive"))
      (node (ref "IC5") (pin "13") (pinfunction "-IN_13") (pintype "input"))
      (node (ref "IC5") (pin "14") (pinfunction "OUT_14") (pintype "output"))
    )
    (net (code "58") (name "Net-(IC6A--IN)") (class "Default")
      (node (ref "D7") (pin "A") (pinfunction "A_A") (pintype "passive"))
      (node (ref "IC6") (pin "1") (pinfunction "OUT_1") (pintype "output"))
      (node (ref "IC6") (pin "2") (pinfunction "-IN_2") (pintype "input"))
    )
    (net (code "59") (name "Net-(IC6B-+IN)") (class "Default")
      (node (ref "C7") (pin "+") (pinfunction "+_+") (pintype "passive"))
      (node (ref "D7") (pin "C") (pinfunction "C_C") (pintype "passive"))
      (node (ref "IC6") (pin "5") (pinfunction "+IN_5") (pintype "input"))
      (node (ref "RV3") (pin "R2") (pinfunction "2_R2") (pintype "passive"))
      (node (ref "RV3") (pin "VAR") (pinfunction "P$1_VAR") (pintype "passive"))
    )
    (net (code "60") (name "Net-(IC6B--IN)") (class "Default")
      (node (ref "IC6") (pin "6") (pinfunction "-IN_6") (pintype "input"))
      (node (ref "IC6") (pin "7") (pinfunction "OUT_7") (pintype "output"))
      (node (ref "R33") (pin "3") (pinfunction "E_3") (pintype "passive"))
      (node (ref "R34") (pin "2") (pinfunction "2_2") (pintype "passive"))
      (node (ref "R39") (pin "1") (pinfunction "1_1") (pintype "passive"))
    )
    (net (code "61") (name "Net-(IC6C-+IN)") (class "Default")
      (node (ref "C8") (pin "+") (pinfunction "+_+") (pintype "passive"))
      (node (ref "D8") (pin "C") (pinfunction "C_C") (pintype "passive"))
      (node (ref "IC6") (pin "10") (pinfunction "+IN_10") (pintype "input"))
      (node (ref "RV4") (pin "R2") (pinfunction "2_R2") (pintype "passive"))
      (node (ref "RV4") (pin "VAR") (pinfunction "P$1_VAR") (pintype "passive"))
    )
    (net (code "62") (name "Net-(IC6C--IN)") (class "Default")
      (node (ref "IC6") (pin "8") (pinfunction "OUT_8") (pintype "output"))
      (node (ref "IC6") (pin "9") (pinfunction "-IN_9") (pintype "input"))
      (node (ref "R35") (pin "3") (pinfunction "E_3") (pintype "passive"))
      (node (ref "R36") (pin "2") (pinfunction "2_2") (pintype "passive"))
      (node (ref "R40") (pin "1") (pinfunction "1_1") (pintype "passive"))
    )
    (net (code "63") (name "Net-(IC6D--IN)") (class "Default")
      (node (ref "D8") (pin "A") (pinfunction "A_A") (pintype "passive"))
      (node (ref "IC6") (pin "13") (pinfunction "-IN_13") (pintype "input"))
      (node (ref "IC6") (pin "14") (pinfunction "OUT_14") (pintype "output"))
    )
    (net (code "64") (name "Net-(J1-PadP$3)") (class "Default")
      (node (ref "J1") (pin "P$3") (pinfunction "P$3_P$3") (pintype "bidirectional"))
      (node (ref "J1") (pin "P$4") (pinfunction "P$4_P$4") (pintype "bidirectional"))
      (node (ref "R30") (pin "1") (pinfunction "1_1") (pintype "passive"))
    )
    (net (code "65") (name "Net-(J2-PadP$3)") (class "Default")
      (node (ref "J2") (pin "P$3") (pinfunction "P$3_P$3") (pintype "bidirectional"))
      (node (ref "J2") (pin "P$4") (pinfunction "P$4_P$4") (pintype "bidirectional"))
      (node (ref "R32") (pin "1") (pinfunction "1_1") (pintype "passive"))
    )
    (net (code "66") (name "Net-(J3-PadP$3)") (class "Default")
      (node (ref "J3") (pin "P$3") (pinfunction "P$3_P$3") (pintype "bidirectional"))
      (node (ref "J3") (pin "P$4") (pinfunction "P$4_P$4") (pintype "bidirectional"))
      (node (ref "R34") (pin "1") (pinfunction "1_1") (pintype "passive"))
    )
    (net (code "67") (name "Net-(J4-PadP$3)") (class "Default")
      (node (ref "J4") (pin "P$3") (pinfunction "P$3_P$3") (pintype "bidirectional"))
      (node (ref "J4") (pin "P$4") (pinfunction "P$4_P$4") (pintype "bidirectional"))
      (node (ref "R36") (pin "1") (pinfunction "1_1") (pintype "passive"))
    )
    (net (code "68") (name "Net-(RV1-1)") (class "Default")
      (node (ref "R25") (pin "2") (pinfunction "2_2") (pintype "passive"))
      (node (ref "RV1") (pin "R1") (pinfunction "1_R1") (pintype "passive"))
    )
    (net (code "69") (name "Net-(RV2-1)") (class "Default")
      (node (ref "R26") (pin "2") (pinfunction "2_2") (pintype "passive"))
      (node (ref "RV2") (pin "R1") (pinfunction "1_R1") (pintype "passive"))
    )
    (net (code "70") (name "Net-(RV3-1)") (class "Default")
      (node (ref "R27") (pin "2") (pinfunction "2_2") (pintype "passive"))
      (node (ref "RV3") (pin "R1") (pinfunction "1_R1") (pintype "passive"))
    )
    (net (code "71") (name "Net-(RV4-1)") (class "Default")
      (node (ref "R28") (pin "2") (pinfunction "2_2") (pintype "passive"))
      (node (ref "RV4") (pin "R1") (pinfunction "1_R1") (pintype "passive"))
    )
  )
)
